# FINAL_BOARD.net
KiCad netlist of a schematic drawn in EAGLE
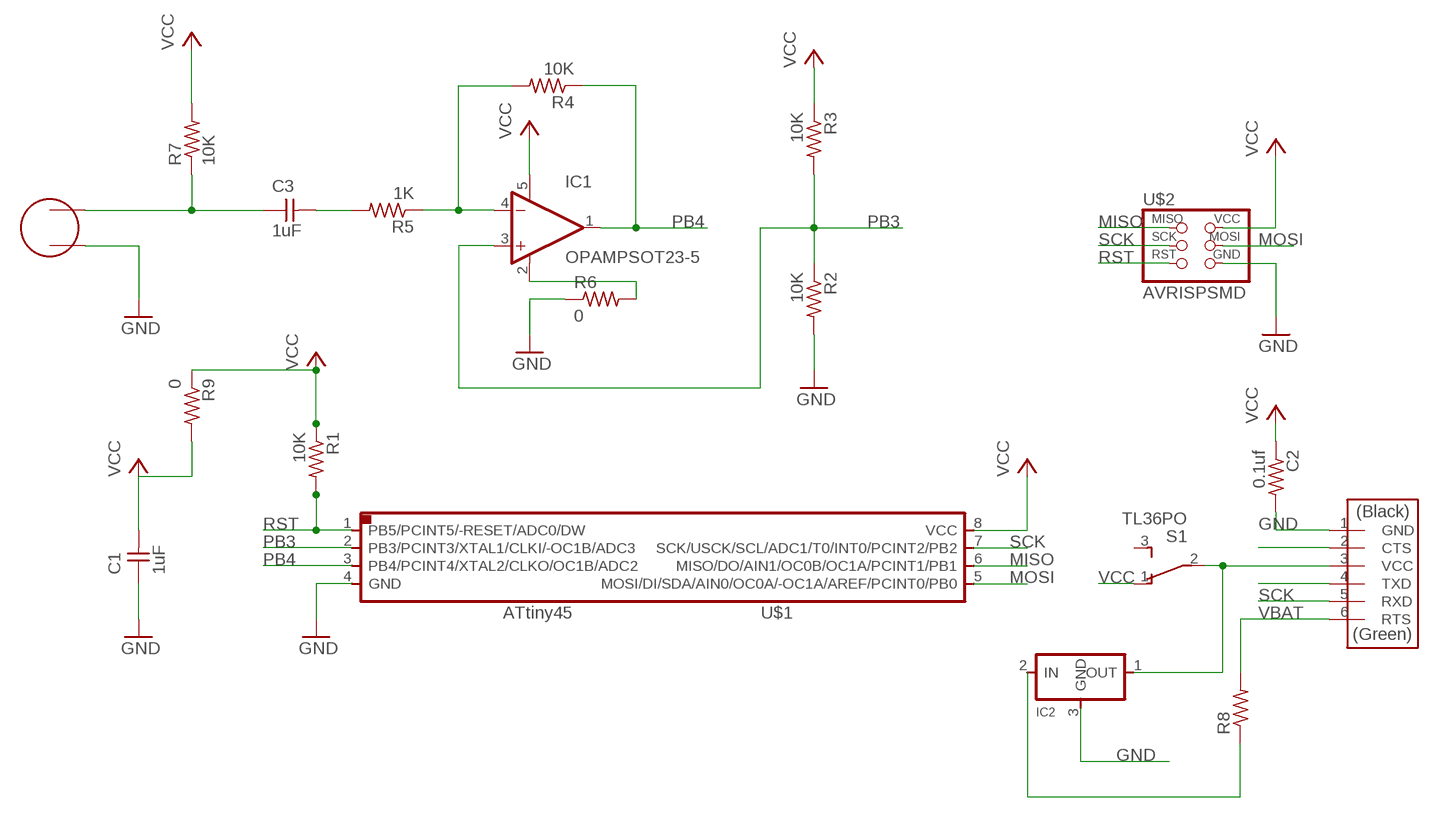
[diagram p0: schematic, sheet 1]

(export (version "E")
  (design (tool "Eeschema 10.0.6"))
  (components
    (comp (ref "C1")
      (value "1uF")
      (footprint "eagle-import:1206")
      (libsource (lib "eagle-import") (part "UNPOLARIZED_CAPACITOR1206"))
    )
    (comp (ref "C2")
      (value "0.1uf")
      (footprint "eagle-import:1206")
      (libsource (lib "eagle-import") (part "RESISTOR1206"))
    )
    (comp (ref "C3")
      (value "1uF")
      (footprint "eagle-import:1206")
      (libsource (lib "eagle-import") (part "UNPOLARIZED_CAPACITOR1206"))
    )
    (comp (ref "IC1")
      (value "OPAMPSOT23-5")
      (footprint "eagle-import:SOT23-5")
      (libsource (lib "eagle-import") (part "OPAMPSOT23-5"))
    )
    (comp (ref "IC2")
      (value "REGULATORSOT23")
      (footprint "eagle-import:SOT23")
      (libsource (lib "eagle-import") (part "REGULATORSOT23"))
    )
    (comp (ref "R1")
      (value "10K")
      (footprint "eagle-import:1206")
      (libsource (lib "eagle-import") (part "RESISTOR1206"))
    )
    (comp (ref "R2")
      (value "10K")
      (footprint "eagle-import:1206")
      (libsource (lib "eagle-import") (part "RESISTOR1206"))
    )
    (comp (ref "R3")
      (value "10K")
      (footprint "eagle-import:1206")
      (libsource (lib "eagle-import") (part "RESISTOR1206"))
    )
    (comp (ref "R4")
      (value "10K")
      (footprint "eagle-import:1206")
      (libsource (lib "eagle-import") (part "RESISTOR1206"))
    )
    (comp (ref "R5")
      (value "1K")
      (footprint "eagle-import:1206")
      (libsource (lib "eagle-import") (part "RESISTOR1206"))
    )
    (comp (ref "R6")
      (value "0")
      (footprint "eagle-import:1206")
      (libsource (lib "eagle-import") (part "RESISTOR1206"))
    )
    (comp (ref "R7")
      (value "10K")
      (footprint "eagle-import:1206")
      (libsource (lib "eagle-import") (part "RESISTOR1206"))
    )
    (comp (ref "R8")
      (value "RES-US1206")
      (footprint "eagle-import:R1206")
      (libsource (lib "eagle-import") (part "RES-US1206"))
    )
    (comp (ref "R9")
      (value "0")
      (footprint "eagle-import:1206")
      (libsource (lib "eagle-import") (part "RESISTOR1206"))
    )
    (comp (ref "S1")
      (value "TL36PO")
      (footprint "eagle-import:TL3XPO")
      (libsource (lib "eagle-import") (part "TL36PO"))
    )
    (comp (ref "U$1")
      (value "ATTINY45SI")
      (footprint "eagle-import:SOIC8")
      (libsource (lib "eagle-import") (part "ATTINY45SI"))
    )
    (comp (ref "U$2")
      (value "AVRISPSMD")
      (footprint "eagle-import:2X03SMD")
      (libsource (lib "eagle-import") (part "AVRISPSMD"))
    )
    (comp (ref "U$3")
      (value "FTDI-SMD-HEADER")
      (footprint "eagle-import:1X06SMD")
      (libsource (lib "eagle-import") (part "FTDI-SMD-HEADER"))
    )
    (comp (ref "U$4")
      (value "ELECTRET")
      (footprint "eagle-import:ELECTRET_2742PBJ-A")
      (libsource (lib "eagle-import") (part "ELECTRET"))
    )
  )
  (nets
    (net (code "1") (name "/MISO") (class "Default")
      (node (ref "U$1") (pin "6") (pinfunction "MISO/DO/AIN1/OC0B/OC1A/PCINT1/PB1_6") (pintype "bidirectional"))
      (node (ref "U$2") (pin "1") (pinfunction "MISO_1") (pintype "passive"))
    )
    (net (code "2") (name "/MOSI") (class "Default")
      (node (ref "U$1") (pin "5") (pinfunction "MOSI/DI/SDA/AIN0/OC0A/-OC1A/AREF/PCINT0/PB0_5") (pintype "bidirectional"))
      (node (ref "U$2") (pin "4") (pinfunction "MOSI_4") (pintype "passive"))
    )
    (net (code "3") (name "/PB3") (class "Default")
      (node (ref "IC1") (pin "3") (pinfunction "+IN_3") (pintype "input"))
      (node (ref "R2") (pin "1") (pinfunction "1_1") (pintype "passive"))
      (node (ref "R3") (pin "2") (pinfunction "2_2") (pintype "passive"))
      (node (ref "U$1") (pin "2") (pinfunction "PB3/PCINT3/XTAL1/CLKI/-OC1B/ADC3_2") (pintype "bidirectional"))
    )
    (net (code "4") (name "/PB4") (class "Default")
      (node (ref "IC1") (pin "1") (pinfunction "OUT_1") (pintype "output"))
      (node (ref "R4") (pin "1") (pinfunction "1_1") (pintype "passive"))
      (node (ref "U$1") (pin "3") (pinfunction "PB4/PCINT4/XTAL2/CLKO/OC1B/ADC2_3") (pintype "bidirectional"))
    )
    (net (code "5") (name "/RST") (class "Default")
      (node (ref "R1") (pin "2") (pinfunction "2_2") (pintype "passive"))
      (node (ref "U$1") (pin "1") (pinfunction "PB5/PCINT5/-RESET/ADC0/DW_1") (pintype "bidirectional"))
      (node (ref "U$2") (pin "5") (pinfunction "RST_5") (pintype "passive"))
    )
    (net (code "6") (name "/SCK") (class "Default")
      (node (ref "U$1") (pin "7") (pinfunction "SCK/USCK/SCL/ADC1/T0/INT0/PCINT2/PB2_7") (pintype "bidirectional"))
      (node (ref "U$2") (pin "3") (pinfunction "SCK_3") (pintype "passive"))
      (node (ref "U$3") (pin "5") (pinfunction "RXD_5") (pintype "bidirectional"))
    )
    (net (code "7") (name "/VBAT") (class "Default")
      (node (ref "R8") (pin "2") (pinfunction "2_2") (pintype "passive"))
      (node (ref "U$3") (pin "6") (pinfunction "RTS_6") (pintype "bidirectional"))
    )
    (net (code "8") (name "GND") (class "Default")
      (node (ref "C1") (pin "1") (pinfunction "1_1") (pintype "passive"))
      (node (ref "C2") (pin "2") (pinfunction "2_2") (pintype "passive"))
      (node (ref "IC2") (pin "3") (pinfunction "GND_3") (pintype "bidirectional"))
      (node (ref "R2") (pin "2") (pinfunction "2_2") (pintype "passive"))
      (node (ref "R6") (pin "1") (pinfunction "1_1") (pintype "passive"))
      (node (ref "U$1") (pin "4") (pinfunction "GND_4") (pintype "bidirectional"))
      (node (ref "U$2") (pin "6") (pinfunction "GND_6") (pintype "passive"))
      (node (ref "U$3") (pin "1") (pinfunction "GND_1") (pintype "bidirectional"))
      (node (ref "U$4") (pin "P$1") (pinfunction "P$1_P$1") (pintype "bidirectional"))
    )
    (net (code "9") (name "Net-(C3-Pad1)") (class "Default")
      (node (ref "C3") (pin "1") (pinfunction "1_1") (pintype "passive"))
      (node (ref "R7") (pin "1") (pinfunction "1_1") (pintype "passive"))
      (node (ref "U$4") (pin "P$2") (pinfunction "P$2_P$2") (pintype "bidirectional"))
    )
    (net (code "10") (name "Net-(C3-Pad2)") (class "Default")
      (node (ref "C3") (pin "2") (pinfunction "2_2") (pintype "passive"))
      (node (ref "R5") (pin "2") (pinfunction "2_2") (pintype "passive"))
    )
    (net (code "11") (name "Net-(IC1--IN)") (class "Default")
      (node (ref "IC1") (pin "4") (pinfunction "-IN_4") (pintype "input"))
      (node (ref "R4") (pin "2") (pinfunction "2_2") (pintype "passive"))
      (node (ref "R5") (pin "1") (pinfunction "1_1") (pintype "passive"))
    )
    (net (code "12") (name "Net-(IC1-V-)") (class "Default")
      (node (ref "IC1") (pin "2") (pinfunction "V-_2") (pintype "power_in"))
      (node (ref "R6") (pin "2") (pinfunction "2_2") (pintype "passive"))
    )
    (net (code "13") (name "Net-(IC2-IN)") (class "Default")
      (node (ref "IC2") (pin "2") (pinfunction "IN_2") (pintype "bidirectional"))
      (node (ref "R8") (pin "1") (pinfunction "1_1") (pintype "passive"))
    )
    (net (code "14") (name "Net-(IC2-OUT)") (class "Default")
      (node (ref "IC2") (pin "1") (pinfunction "OUT_1") (pintype "bidirectional"))
      (node (ref "S1") (pin "2") (pinfunction "P_2") (pintype "passive"))
      (node (ref "U$3") (pin "3") (pinfunction "VCC_3") (pintype "bidirectional"))
    )
    (net (code "15") (name "VCC") (class "Default")
      (node (ref "C1") (pin "2") (pinfunction "2_2") (pintype "passive"))
      (node (ref "C2") (pin "1") (pinfunction "1_1") (pintype "passive"))
      (node (ref "IC1") (pin "5") (pinfunction "V+_5") (pintype "power_in"))
      (node (ref "R1") (pin "1") (pinfunction "1_1") (pintype "passive"))
      (node (ref "R3") (pin "1") (pinfunction "1_1") (pintype "passive"))
      (node (ref "R7") (pin "2") (pinfunction "2_2") (pintype "passive"))
      (node (ref "R9") (pin "1") (pinfunction "1_1") (pintype "passive"))
      (node (ref "R9") (pin "2") (pinfunction "2_2") (pintype "passive"))
      (node (ref "S1") (pin "1") (pinfunction "O_1") (pintype "passive"))
      (node (ref "U$1") (pin "8") (pinfunction "VCC_8") (pintype "bidirectional"))
      (node (ref "U$2") (pin "2") (pinfunction "VCC_2") (pintype "passive"))
    )
    (net (code "16") (name "unconnected-(S1-S-Pad3)") (class "Default")
      (node (ref "S1") (pin "3") (pinfunction "S_3") (pintype "passive"))
    )
    (net (code "17") (name "unconnected-(U$3-CTS-Pad2)") (class "Default")
      (node (ref "U$3") (pin "2") (pinfunction "CTS_2") (pintype "bidirectional"))
    )
    (net (code "18") (name "unconnected-(U$3-TXD-Pad4)") (class "Default")
      (node (ref "U$3") (pin "4") (pinfunction "TXD_4") (pintype "bidirectional"))
    )
  )
)
